# dplus.net
KiCad netlist of a schematic drawn in EAGLE
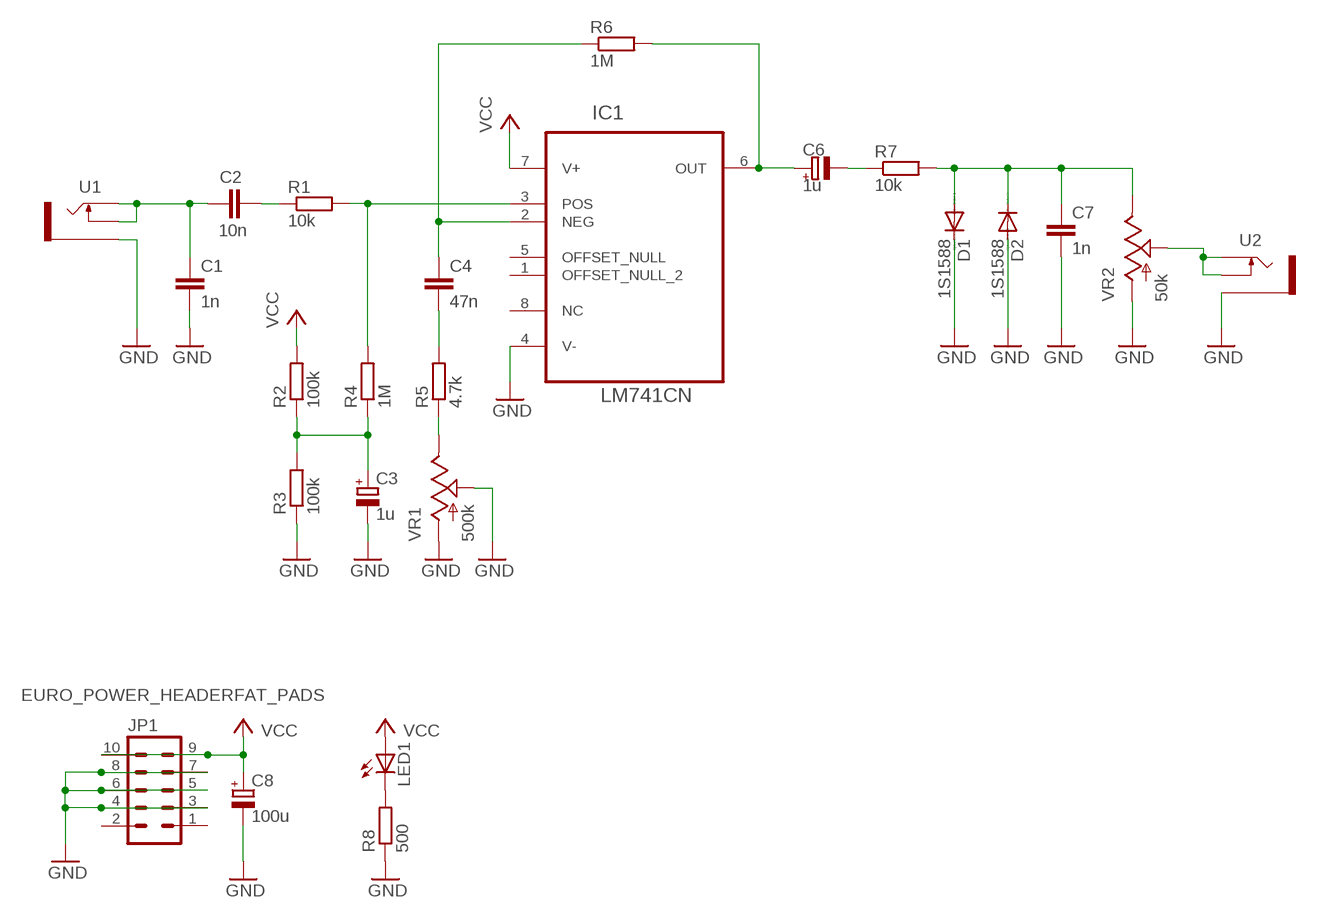
[diagram p0: schematic, sheet 1]

(export (version "E")
  (design (tool "Eeschema 10.0.6"))
  (components
    (comp (ref "C1")
      (value "1n")
      (footprint "eagle-import:C050-025X075")
      (libsource (lib "eagle-import") (part "C-EU050-025X075"))
    )
    (comp (ref "C2")
      (value "10n")
      (footprint "eagle-import:C050-035X075")
      (libsource (lib "eagle-import") (part "C-EU050-035X075"))
    )
    (comp (ref "C3")
      (value "1u")
      (footprint "eagle-import:E2,5-5")
      (libsource (lib "eagle-import") (part "CPOL-EUE2.5-5"))
    )
    (comp (ref "C4")
      (value "47n")
      (footprint "eagle-import:C050-045X075")
      (libsource (lib "eagle-import") (part "C-EU050-045X075"))
    )
    (comp (ref "C6")
      (value "1u")
      (footprint "eagle-import:E2,5-5")
      (libsource (lib "eagle-import") (part "CPOL-EUE2.5-5"))
    )
    (comp (ref "C7")
      (value "1n")
      (footprint "eagle-import:C050-025X075")
      (libsource (lib "eagle-import") (part "C-EU050-025X075"))
    )
    (comp (ref "C8")
      (value "100u")
      (footprint "eagle-import:E2-4")
      (libsource (lib "eagle-import") (part "CPOL-EUE2-4"))
    )
    (comp (ref "D1")
      (value "1S1588")
      (footprint "eagle-import:D-5")
      (libsource (lib "eagle-import") (part "DIODE-D-5"))
    )
    (comp (ref "D2")
      (value "1S1588")
      (footprint "eagle-import:D-5")
      (libsource (lib "eagle-import") (part "DIODE-D-5"))
    )
    (comp (ref "IC1")
      (value "LM741CN")
      (footprint "eagle-import:DIP254P762X508-8")
      (fields (field (name "MF") "Texas Instruments") (field (name "MP") "LM741CN/NOPB"))
      (libsource (lib "eagle-import") (part "LM741CN"))
    )
    (comp (ref "JP1")
      (value "EURO_POWER_HEADERFAT_PADS")
      (footprint "eagle-import:EURO_PWR_HEADER_FAT")
      (libsource (lib "eagle-import") (part "EURO_POWER_HEADERFAT_PADS"))
    )
    (comp (ref "LED1")
      (value "LED3MM")
      (footprint "eagle-import:LED3MM")
      (libsource (lib "eagle-import") (part "LED3MM"))
    )
    (comp (ref "R1")
      (value "10k")
      (footprint "eagle-import:R1206W")
      (libsource (lib "eagle-import") (part "R-EU_R1206W"))
    )
    (comp (ref "R2")
      (value "100k")
      (footprint "eagle-import:R1206W")
      (libsource (lib "eagle-import") (part "R-EU_R1206W"))
    )
    (comp (ref "R3")
      (value "100k")
      (footprint "eagle-import:R1206W")
      (libsource (lib "eagle-import") (part "R-EU_R1206W"))
    )
    (comp (ref "R4")
      (value "1M")
      (footprint "eagle-import:R1206W")
      (libsource (lib "eagle-import") (part "R-EU_R1206W"))
    )
    (comp (ref "R5")
      (value "4.7k")
      (footprint "eagle-import:R1206W")
      (libsource (lib "eagle-import") (part "R-EU_R1206W"))
    )
    (comp (ref "R6")
      (value "1M")
      (footprint "eagle-import:R1206W")
      (libsource (lib "eagle-import") (part "R-EU_R1206W"))
    )
    (comp (ref "R7")
      (value "10k")
      (footprint "eagle-import:R1206W")
      (libsource (lib "eagle-import") (part "R-EU_R1206W"))
    )
    (comp (ref "R8")
      (value "500")
      (footprint "eagle-import:R1206W")
      (libsource (lib "eagle-import") (part "R-EU_R1206W"))
    )
    (comp (ref "U1")
      (value "THONKICONNOLD")
      (footprint "eagle-import:THONKICONN")
      (libsource (lib "eagle-import") (part "THONKICONNOLD"))
    )
    (comp (ref "U2")
      (value "THONKICONNOLD")
      (footprint "eagle-import:THONKICONN")
      (libsource (lib "eagle-import") (part "THONKICONNOLD"))
    )
    (comp (ref "VR1")
      (value "500k")
      (footprint "eagle-import:9MM_SNAP-IN_POT")
      (libsource (lib "eagle-import") (part "9MM_SNAP-IN_POT_"))
    )
    (comp (ref "VR2")
      (value "50k")
      (footprint "eagle-import:9MM_SNAP-IN_POT")
      (libsource (lib "eagle-import") (part "9MM_SNAP-IN_POT_"))
    )
  )
  (nets
    (net (code "1") (name "GND") (class "Default")
      (node (ref "C1") (pin "2") (pinfunction "2_2") (pintype "passive"))
      (node (ref "C3") (pin "-") (pinfunction "-_-") (pintype "passive"))
      (node (ref "C7") (pin "2") (pinfunction "2_2") (pintype "passive"))
      (node (ref "C8") (pin "-") (pinfunction "-_-") (pintype "passive"))
      (node (ref "D1") (pin "C") (pinfunction "C_C") (pintype "passive"))
      (node (ref "D2") (pin "A") (pinfunction "A_A") (pintype "passive"))
      (node (ref "IC1") (pin "4") (pinfunction "V-_4") (pintype "power_in"))
      (node (ref "JP1") (pin "3") (pinfunction "3_3") (pintype "passive"))
      (node (ref "JP1") (pin "4") (pinfunction "4_4") (pintype "passive"))
      (node (ref "JP1") (pin "5") (pinfunction "5_5") (pintype "passive"))
      (node (ref "JP1") (pin "6") (pinfunction "6_6") (pintype "passive"))
      (node (ref "JP1") (pin "7") (pinfunction "7_7") (pintype "passive"))
      (node (ref "JP1") (pin "8") (pinfunction "8_8") (pintype "passive"))
      (node (ref "R3") (pin "1") (pinfunction "1_1") (pintype "passive"))
      (node (ref "R8") (pin "1") (pinfunction "1_1") (pintype "passive"))
      (node (ref "U1") (pin "P$1_SLEEVE") (pinfunction "SLEEVE_P$1_SLEEVE") (pintype "passive"))
      (node (ref "U2") (pin "P$1_SLEEVE") (pinfunction "SLEEVE_P$1_SLEEVE") (pintype "passive"))
      (node (ref "VR1") (pin "1") (pinfunction "A_1") (pintype "passive"))
      (node (ref "VR1") (pin "2") (pinfunction "S_2") (pintype "passive"))
      (node (ref "VR2") (pin "1") (pinfunction "A_1") (pintype "passive"))
    )
    (net (code "2") (name "Net-(C2-Pad2)") (class "Default")
      (node (ref "C2") (pin "2") (pinfunction "2_2") (pintype "passive"))
      (node (ref "R1") (pin "1") (pinfunction "1_1") (pintype "passive"))
    )
    (net (code "3") (name "Net-(C3-Pad+)") (class "Default")
      (node (ref "C3") (pin "+") (pinfunction "+_+") (pintype "passive"))
      (node (ref "R2") (pin "1") (pinfunction "1_1") (pintype "passive"))
      (node (ref "R3") (pin "2") (pinfunction "2_2") (pintype "passive"))
      (node (ref "R4") (pin "1") (pinfunction "1_1") (pintype "passive"))
    )
    (net (code "4") (name "Net-(C4-Pad2)") (class "Default")
      (node (ref "C4") (pin "2") (pinfunction "2_2") (pintype "passive"))
      (node (ref "R5") (pin "2") (pinfunction "2_2") (pintype "passive"))
    )
    (net (code "5") (name "Net-(C6-Pad-)") (class "Default")
      (node (ref "C6") (pin "-") (pinfunction "-_-") (pintype "passive"))
      (node (ref "R7") (pin "1") (pinfunction "1_1") (pintype "passive"))
    )
    (net (code "6") (name "Net-(IC1-NEG)") (class "Default")
      (node (ref "C4") (pin "1") (pinfunction "1_1") (pintype "passive"))
      (node (ref "IC1") (pin "2") (pinfunction "NEG_2") (pintype "input"))
      (node (ref "R6") (pin "1") (pinfunction "1_1") (pintype "passive"))
    )
    (net (code "7") (name "Net-(IC1-OUT)") (class "Default")
      (node (ref "C6") (pin "+") (pinfunction "+_+") (pintype "passive"))
      (node (ref "IC1") (pin "6") (pinfunction "OUT_6") (pintype "output"))
      (node (ref "R6") (pin "2") (pinfunction "2_2") (pintype "passive"))
    )
    (net (code "8") (name "Net-(IC1-POS)") (class "Default")
      (node (ref "IC1") (pin "3") (pinfunction "POS_3") (pintype "input"))
      (node (ref "R1") (pin "2") (pinfunction "2_2") (pintype "passive"))
      (node (ref "R4") (pin "2") (pinfunction "2_2") (pintype "passive"))
    )
    (net (code "9") (name "Net-(LED1-C)") (class "Default")
      (node (ref "LED1") (pin "K") (pinfunction "C_K") (pintype "passive"))
      (node (ref "R8") (pin "2") (pinfunction "2_2") (pintype "passive"))
    )
    (net (code "10") (name "Net-(U1-SWITCH)") (class "Default")
      (node (ref "C1") (pin "1") (pinfunction "1_1") (pintype "passive"))
      (node (ref "C2") (pin "1") (pinfunction "1_1") (pintype "passive"))
      (node (ref "U1") (pin "P$2_SWITCH") (pinfunction "SWITCH_P$2_SWITCH") (pintype "passive"))
      (node (ref "U1") (pin "P$3_TIP") (pinfunction "TIP_P$3_TIP") (pintype "passive"))
    )
    (net (code "11") (name "Net-(U2-SWITCH)") (class "Default")
      (node (ref "U2") (pin "P$2_SWITCH") (pinfunction "SWITCH_P$2_SWITCH") (pintype "passive"))
      (node (ref "U2") (pin "P$3_TIP") (pinfunction "TIP_P$3_TIP") (pintype "passive"))
      (node (ref "VR2") (pin "2") (pinfunction "S_2") (pintype "passive"))
    )
    (net (code "12") (name "Net-(VR1-E)") (class "Default")
      (node (ref "R5") (pin "1") (pinfunction "1_1") (pintype "passive"))
      (node (ref "VR1") (pin "3") (pinfunction "E_3") (pintype "passive"))
    )
    (net (code "13") (name "Net-(VR2-E)") (class "Default")
      (node (ref "C7") (pin "1") (pinfunction "1_1") (pintype "passive"))
      (node (ref "D1") (pin "A") (pinfunction "A_A") (pintype "passive"))
      (node (ref "D2") (pin "C") (pinfunction "C_C") (pintype "passive"))
      (node (ref "R7") (pin "2") (pinfunction "2_2") (pintype "passive"))
      (node (ref "VR2") (pin "3") (pinfunction "E_3") (pintype "passive"))
    )
    (net (code "14") (name "VCC") (class "Default")
      (node (ref "C8") (pin "+") (pinfunction "+_+") (pintype "passive"))
      (node (ref "IC1") (pin "7") (pinfunction "V+_7") (pintype "power_in"))
      (node (ref "JP1") (pin "10") (pinfunction "10_10") (pintype "passive"))
      (node (ref "JP1") (pin "9") (pinfunction "9_9") (pintype "passive"))
      (node (ref "LED1") (pin "A") (pinfunction "A_A") (pintype "passive"))
      (node (ref "R2") (pin "2") (pinfunction "2_2") (pintype "passive"))
    )
    (net (code "15") (name "unconnected-(IC1-NC-Pad8)") (class "Default")
      (node (ref "IC1") (pin "8") (pinfunction "NC_8") (pintype "no_connect"))
    )
    (net (code "16") (name "unconnected-(IC1-OFFSET_NULL-Pad5)") (class "Default")
      (node (ref "IC1") (pin "5") (pinfunction "OFFSET_NULL_5") (pintype "passive"))
    )
    (net (code "17") (name "unconnected-(IC1-OFFSET_NULL_2-Pad1)") (class "Default")
      (node (ref "IC1") (pin "1") (pinfunction "OFFSET_NULL_2_1") (pintype "passive"))
    )
    (net (code "18") (name "unconnected-(JP1-Pad1)") (class "Default")
      (node (ref "JP1") (pin "1") (pinfunction "1_1") (pintype "passive"))
    )
    (net (code "19") (name "unconnected-(JP1-Pad2)") (class "Default")
      (node (ref "JP1") (pin "2") (pinfunction "2_2") (pintype "passive"))
    )
  )
)
